# Distributer.net
KiCad netlist of a schematic drawn in EAGLE
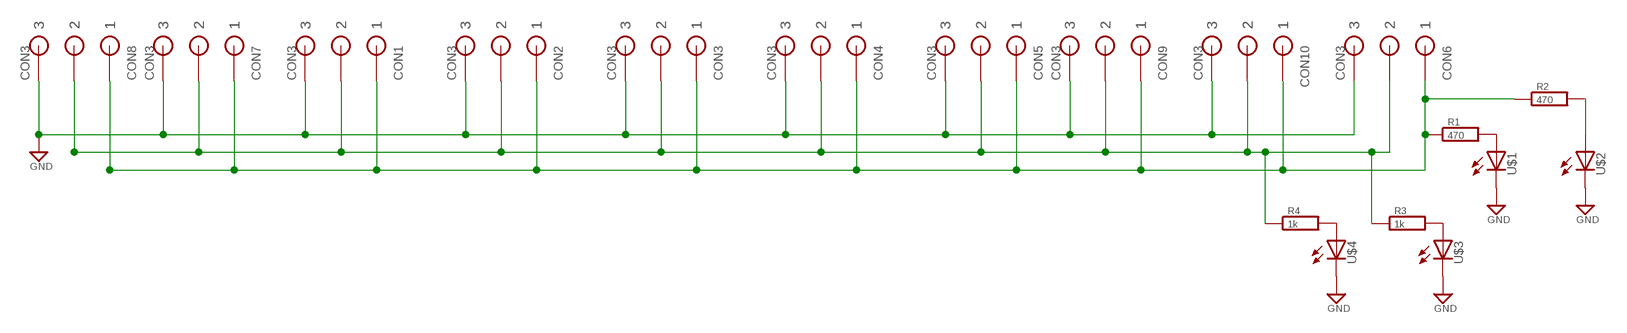
[diagram p0: schematic, sheet 1]

(export (version "E")
  (design (tool "Eeschema 10.0.6"))
  (components
    (comp (ref "CON1")
      (value "CON3")
      (footprint "eagle-import:CON3")
      (libsource (lib "eagle-import") (part "CON3"))
    )
    (comp (ref "CON2")
      (value "CON3")
      (footprint "eagle-import:CON3")
      (libsource (lib "eagle-import") (part "CON3"))
    )
    (comp (ref "CON3")
      (value "CON3")
      (footprint "eagle-import:CON3")
      (libsource (lib "eagle-import") (part "CON3"))
    )
    (comp (ref "CON4")
      (value "CON3")
      (footprint "eagle-import:CON3")
      (libsource (lib "eagle-import") (part "CON3"))
    )
    (comp (ref "CON5")
      (value "CON3")
      (footprint "eagle-import:CON3")
      (libsource (lib "eagle-import") (part "CON3"))
    )
    (comp (ref "CON6")
      (value "CON3")
      (footprint "eagle-import:CON3")
      (libsource (lib "eagle-import") (part "CON3"))
    )
    (comp (ref "CON7")
      (value "CON3")
      (footprint "eagle-import:CON3")
      (libsource (lib "eagle-import") (part "CON3"))
    )
    (comp (ref "CON8")
      (value "CON3")
      (footprint "eagle-import:CON3")
      (libsource (lib "eagle-import") (part "CON3"))
    )
    (comp (ref "CON9")
      (value "CON3")
      (footprint "eagle-import:CON3")
      (libsource (lib "eagle-import") (part "CON3"))
    )
    (comp (ref "CON10")
      (value "CON3")
      (footprint "eagle-import:CON3")
      (libsource (lib "eagle-import") (part "CON3"))
    )
    (comp (ref "R1")
      (value "470")
      (footprint "eagle-import:0805")
      (libsource (lib "eagle-import") (part "抵抗0805"))
    )
    (comp (ref "R2")
      (value "470")
      (footprint "eagle-import:0805")
      (libsource (lib "eagle-import") (part "抵抗0805"))
    )
    (comp (ref "R3")
      (value "1k")
      (footprint "eagle-import:0805")
      (libsource (lib "eagle-import") (part "抵抗0805"))
    )
    (comp (ref "R4")
      (value "1k")
      (footprint "eagle-import:0805")
      (libsource (lib "eagle-import") (part "抵抗0805"))
    )
    (comp (ref "U$1")
      (value "LED(砲弾型)3")
      (footprint "eagle-import:LED3MM")
      (libsource (lib "eagle-import") (part "LED(砲弾型)3"))
    )
    (comp (ref "U$2")
      (value "LED(砲弾型)3")
      (footprint "eagle-import:LED3MM")
      (libsource (lib "eagle-import") (part "LED(砲弾型)3"))
    )
    (comp (ref "U$3")
      (value "LED(砲弾型)3")
      (footprint "eagle-import:LED3MM")
      (libsource (lib "eagle-import") (part "LED(砲弾型)3"))
    )
    (comp (ref "U$4")
      (value "LED(砲弾型)3")
      (footprint "eagle-import:LED3MM")
      (libsource (lib "eagle-import") (part "LED(砲弾型)3"))
    )
  )
  (nets
    (net (code "1") (name "GND") (class "Default")
      (node (ref "CON1") (pin "P$3") (pinfunction "3_P$3") (pintype "bidirectional"))
      (node (ref "CON10") (pin "P$3") (pinfunction "3_P$3") (pintype "bidirectional"))
      (node (ref "CON2") (pin "P$3") (pinfunction "3_P$3") (pintype "bidirectional"))
      (node (ref "CON3") (pin "P$3") (pinfunction "3_P$3") (pintype "bidirectional"))
      (node (ref "CON4") (pin "P$3") (pinfunction "3_P$3") (pintype "bidirectional"))
      (node (ref "CON5") (pin "P$3") (pinfunction "3_P$3") (pintype "bidirectional"))
      (node (ref "CON6") (pin "P$3") (pinfunction "3_P$3") (pintype "bidirectional"))
      (node (ref "CON7") (pin "P$3") (pinfunction "3_P$3") (pintype "bidirectional"))
      (node (ref "CON8") (pin "P$3") (pinfunction "3_P$3") (pintype "bidirectional"))
      (node (ref "CON9") (pin "P$3") (pinfunction "3_P$3") (pintype "bidirectional"))
      (node (ref "U$1") (pin "K") (pinfunction "K_K") (pintype "passive"))
      (node (ref "U$2") (pin "K") (pinfunction "K_K") (pintype "passive"))
      (node (ref "U$3") (pin "K") (pinfunction "K_K") (pintype "passive"))
      (node (ref "U$4") (pin "K") (pinfunction "K_K") (pintype "passive"))
    )
    (net (code "2") (name "Net-(CON1-1)") (class "Default")
      (node (ref "CON1") (pin "P$1") (pinfunction "1_P$1") (pintype "bidirectional"))
      (node (ref "CON10") (pin "P$1") (pinfunction "1_P$1") (pintype "bidirectional"))
      (node (ref "CON2") (pin "P$1") (pinfunction "1_P$1") (pintype "bidirectional"))
      (node (ref "CON3") (pin "P$1") (pinfunction "1_P$1") (pintype "bidirectional"))
      (node (ref "CON4") (pin "P$1") (pinfunction "1_P$1") (pintype "bidirectional"))
      (node (ref "CON5") (pin "P$1") (pinfunction "1_P$1") (pintype "bidirectional"))
      (node (ref "CON6") (pin "P$1") (pinfunction "1_P$1") (pintype "bidirectional"))
      (node (ref "CON7") (pin "P$1") (pinfunction "1_P$1") (pintype "bidirectional"))
      (node (ref "CON8") (pin "P$1") (pinfunction "1_P$1") (pintype "bidirectional"))
      (node (ref "CON9") (pin "P$1") (pinfunction "1_P$1") (pintype "bidirectional"))
      (node (ref "R1") (pin "1") (pinfunction "1_1") (pintype "passive"))
      (node (ref "R2") (pin "1") (pinfunction "1_1") (pintype "passive"))
    )
    (net (code "3") (name "Net-(CON1-2)") (class "Default")
      (node (ref "CON1") (pin "P$2") (pinfunction "2_P$2") (pintype "bidirectional"))
      (node (ref "CON10") (pin "P$2") (pinfunction "2_P$2") (pintype "bidirectional"))
      (node (ref "CON2") (pin "P$2") (pinfunction "2_P$2") (pintype "bidirectional"))
      (node (ref "CON3") (pin "P$2") (pinfunction "2_P$2") (pintype "bidirectional"))
      (node (ref "CON4") (pin "P$2") (pinfunction "2_P$2") (pintype "bidirectional"))
      (node (ref "CON5") (pin "P$2") (pinfunction "2_P$2") (pintype "bidirectional"))
      (node (ref "CON6") (pin "P$2") (pinfunction "2_P$2") (pintype "bidirectional"))
      (node (ref "CON7") (pin "P$2") (pinfunction "2_P$2") (pintype "bidirectional"))
      (node (ref "CON8") (pin "P$2") (pinfunction "2_P$2") (pintype "bidirectional"))
      (node (ref "CON9") (pin "P$2") (pinfunction "2_P$2") (pintype "bidirectional"))
      (node (ref "R3") (pin "1") (pinfunction "1_1") (pintype "passive"))
      (node (ref "R4") (pin "1") (pinfunction "1_1") (pintype "passive"))
    )
    (net (code "4") (name "Net-(R1-Pad2)") (class "Default")
      (node (ref "R1") (pin "2") (pinfunction "2_2") (pintype "passive"))
      (node (ref "U$1") (pin "A") (pinfunction "A_A") (pintype "passive"))
    )
    (net (code "5") (name "Net-(R2-Pad2)") (class "Default")
      (node (ref "R2") (pin "2") (pinfunction "2_2") (pintype "passive"))
      (node (ref "U$2") (pin "A") (pinfunction "A_A") (pintype "passive"))
    )
    (net (code "6") (name "Net-(R3-Pad2)") (class "Default")
      (node (ref "R3") (pin "2") (pinfunction "2_2") (pintype "passive"))
      (node (ref "U$3") (pin "A") (pinfunction "A_A") (pintype "passive"))
    )
    (net (code "7") (name "Net-(R4-Pad2)") (class "Default")
      (node (ref "R4") (pin "2") (pinfunction "2_2") (pintype "passive"))
      (node (ref "U$4") (pin "A") (pinfunction "A_A") (pintype "passive"))
    )
  )
)
